# Command.net
KiCad netlist of a schematic drawn in Altium Designer
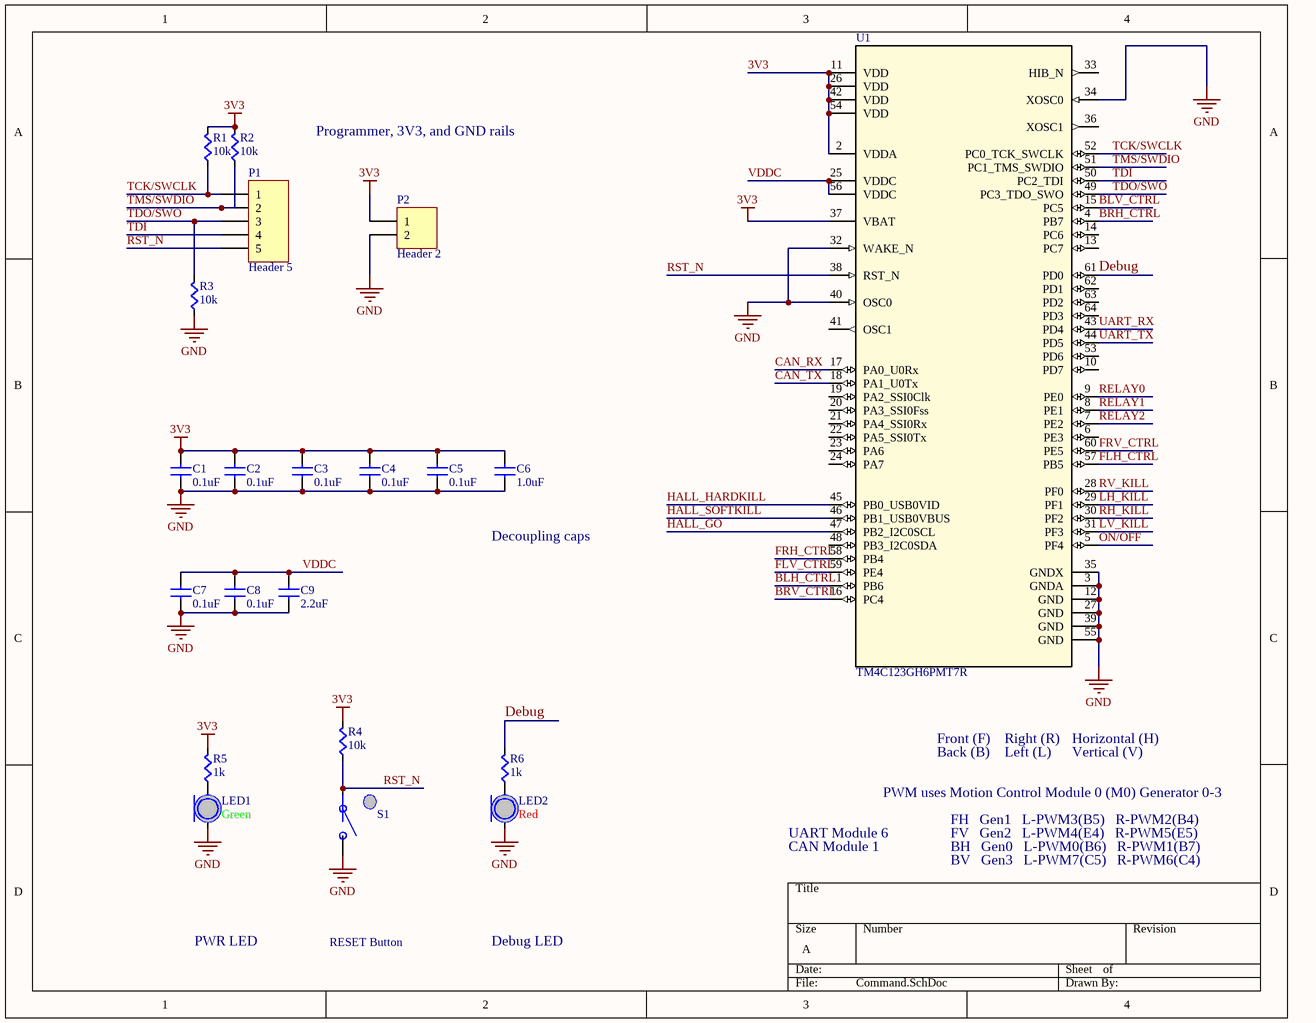
[diagram p0: Command.SchDoc]

(export (version "E")
  (design (tool "Eeschema 10.0.6"))
  (components
    (comp (ref "C1")
      (value "0.1uF")
      (footprint "CAPC0603")
      (fields (field (name "Comment") "Cap"))
      (libsource (lib "SubjuGator8") (part "Cap"))
    )
    (comp (ref "C2")
      (value "0.1uF")
      (footprint "CAPC0603")
      (fields (field (name "Comment") "Cap"))
      (libsource (lib "SubjuGator8") (part "Cap"))
    )
    (comp (ref "C3")
      (value "0.1uF")
      (footprint "CAPC0603")
      (fields (field (name "Comment") "Cap"))
      (libsource (lib "SubjuGator8") (part "Cap"))
    )
    (comp (ref "C4")
      (value "0.1uF")
      (footprint "CAPC0603")
      (fields (field (name "Comment") "Cap"))
      (libsource (lib "SubjuGator8") (part "Cap"))
    )
    (comp (ref "C5")
      (value "0.1uF")
      (footprint "CAPC0603")
      (fields (field (name "Comment") "Cap"))
      (libsource (lib "SubjuGator8") (part "Cap"))
    )
    (comp (ref "C6")
      (value "1.0uF")
      (footprint "CAPC0603")
      (fields (field (name "Comment") "Cap"))
      (libsource (lib "SubjuGator8") (part "Cap"))
    )
    (comp (ref "C7")
      (value "0.1uF")
      (footprint "CAPC0603")
      (fields (field (name "Comment") "Cap"))
      (libsource (lib "SubjuGator8") (part "Cap"))
    )
    (comp (ref "C8")
      (value "0.1uF")
      (footprint "CAPC0603")
      (fields (field (name "Comment") "Cap"))
      (libsource (lib "SubjuGator8") (part "Cap"))
    )
    (comp (ref "C9")
      (value "2.2uF")
      (footprint "CAPC0603")
      (fields (field (name "Comment") "Cap"))
      (libsource (lib "SubjuGator8") (part "Cap"))
    )
    (comp (ref "LED1")
      (value "LED")
      (footprint "LED0603")
      (fields (field (name "COLOR") "Green"))
      (libsource (lib "SubjuGator8") (part "LED"))
    )
    (comp (ref "LED2")
      (value "LED")
      (footprint "LED0603")
      (fields (field (name "COLOR") "Red"))
      (libsource (lib "SubjuGator8") (part "LED"))
    )
    (comp (ref "P1")
      (value "Header 5")
      (footprint "HDR1X5")
      (description "Header, 5-Pin")
      (fields (field (name "PUBLISHER") "Altium Limited"))
      (libsource (lib "Miscellaneous Connectors") (part "Header 5"))
    )
    (comp (ref "P2")
      (value "Header 2")
      (footprint "HDR1X2")
      (description "Header, 2-Pin")
      (fields (field (name "PUBLISHER") "Altium Limited"))
      (libsource (lib "Miscellaneous Connectors") (part "Header 2"))
    )
    (comp (ref "R1")
      (value "10k")
      (footprint "RES0603")
      (fields (field (name "Comment") "Res"))
      (libsource (lib "SubjuGator8") (part "Res"))
    )
    (comp (ref "R2")
      (value "10k")
      (footprint "RES0603")
      (fields (field (name "Comment") "Res"))
      (libsource (lib "SubjuGator8") (part "Res"))
    )
    (comp (ref "R3")
      (value "10k")
      (footprint "RES0603")
      (fields (field (name "Comment") "Res"))
      (libsource (lib "SubjuGator8") (part "Res"))
    )
    (comp (ref "R4")
      (value "10k")
      (footprint "RES0603")
      (fields (field (name "Comment") "Res"))
      (libsource (lib "SubjuGator8") (part "Res"))
    )
    (comp (ref "R5")
      (value "1k")
      (footprint "RES0603")
      (fields (field (name "Comment") "Res"))
      (libsource (lib "SubjuGator8") (part "Res"))
    )
    (comp (ref "R6")
      (value "1k")
      (footprint "RES0603")
      (fields (field (name "Comment") "Res"))
      (libsource (lib "SubjuGator8") (part "Res"))
    )
    (comp (ref "S1")
      (value "Button")
      (footprint "PTS645xxxxSMTR92")
      (description "SPST Button")
      (libsource (lib "SubjuGator8") (part "Button"))
    )
    (comp (ref "U1")
      (value "TM4C123GH6PMT7R")
      (footprint "TM4C123GH6PMT7R_M")
      (description "Imported")
      (fields
        (field (name "PARTNUMBER") "TM4C123GH6PMTR")
        (field (name "ALTERNATE_PARTNUMBER") "TM4C123GH6PMT")
      )
      (libsource (lib "2018-10-31_17-53-54") (part "TM4C123GH6PMT7R"))
    )
  )
  (nets
    (net (code "1") (name "/BLH_CTRL") (class "Default")
      (node (ref "U1") (pin "1") (pinfunction "PB6_1") (pintype "bidirectional"))
    )
    (net (code "2") (name "/BLV_CTRL") (class "Default")
      (node (ref "U1") (pin "15") (pinfunction "PC5_15") (pintype "bidirectional"))
    )
    (net (code "3") (name "/BRH_CTRL") (class "Default")
      (node (ref "U1") (pin "4") (pinfunction "PB7_4") (pintype "bidirectional"))
    )
    (net (code "4") (name "/BRV_CTRL") (class "Default")
      (node (ref "U1") (pin "16") (pinfunction "PC4_16") (pintype "bidirectional"))
    )
    (net (code "5") (name "/CAN_RX") (class "Default")
      (node (ref "U1") (pin "17") (pinfunction "PA0_U0Rx_17") (pintype "bidirectional"))
    )
    (net (code "6") (name "/CAN_TX") (class "Default")
      (node (ref "U1") (pin "18") (pinfunction "PA1_U0Tx_18") (pintype "bidirectional"))
    )
    (net (code "7") (name "/Debug") (class "Default")
      (node (ref "R6") (pin "1") (pinfunction "A_1") (pintype "passive"))
      (node (ref "U1") (pin "61") (pinfunction "PD0_61") (pintype "bidirectional"))
    )
    (net (code "8") (name "/FLH_CTRL") (class "Default")
      (node (ref "U1") (pin "57") (pinfunction "PB5_57") (pintype "bidirectional"))
    )
    (net (code "9") (name "/FLV_CTRL") (class "Default")
      (node (ref "U1") (pin "59") (pinfunction "PE4_59") (pintype "bidirectional"))
    )
    (net (code "10") (name "/FRH_CTRL") (class "Default")
      (node (ref "U1") (pin "58") (pinfunction "PB4_58") (pintype "bidirectional"))
    )
    (net (code "11") (name "/FRV_CTRL") (class "Default")
      (node (ref "U1") (pin "60") (pinfunction "PE5_60") (pintype "bidirectional"))
    )
    (net (code "12") (name "/HALL_GO") (class "Default")
      (node (ref "U1") (pin "47") (pinfunction "PB2_I2C0SCL_47") (pintype "bidirectional"))
    )
    (net (code "13") (name "/HALL_HARDKILL") (class "Default")
      (node (ref "U1") (pin "45") (pinfunction "PB0_USB0VID_45") (pintype "bidirectional"))
    )
    (net (code "14") (name "/HALL_SOFTKILL") (class "Default")
      (node (ref "U1") (pin "46") (pinfunction "PB1_USB0VBUS_46") (pintype "bidirectional"))
    )
    (net (code "15") (name "/LH_KILL") (class "Default")
      (node (ref "U1") (pin "29") (pinfunction "PF1_29") (pintype "bidirectional"))
    )
    (net (code "16") (name "/LV_KILL") (class "Default")
      (node (ref "U1") (pin "31") (pinfunction "PF3_31") (pintype "bidirectional"))
    )
    (net (code "17") (name "/ON{slash}OFF") (class "Default")
      (node (ref "U1") (pin "5") (pinfunction "PF4_5") (pintype "bidirectional"))
    )
    (net (code "18") (name "/RELAY0") (class "Default")
      (node (ref "U1") (pin "9") (pinfunction "PE0_9") (pintype "bidirectional"))
    )
    (net (code "19") (name "/RELAY1") (class "Default")
      (node (ref "U1") (pin "8") (pinfunction "PE1_8") (pintype "bidirectional"))
    )
    (net (code "20") (name "/RELAY2") (class "Default")
      (node (ref "U1") (pin "7") (pinfunction "PE2_7") (pintype "bidirectional"))
    )
    (net (code "21") (name "/RH_KILL") (class "Default")
      (node (ref "U1") (pin "30") (pinfunction "PF2_30") (pintype "bidirectional"))
    )
    (net (code "22") (name "/RST_N") (class "Default")
      (node (ref "P1") (pin "5") (pinfunction "5_5") (pintype "passive"))
      (node (ref "R4") (pin "2") (pinfunction "B_2") (pintype "passive"))
      (node (ref "S1") (pin "A") (pinfunction "A_A") (pintype "passive"))
      (node (ref "U1") (pin "38") (pinfunction "RST_N_38") (pintype "input"))
    )
    (net (code "23") (name "/RV_KILL") (class "Default")
      (node (ref "U1") (pin "28") (pinfunction "PF0_28") (pintype "bidirectional"))
    )
    (net (code "24") (name "/TCK{slash}SWCLK") (class "Default")
      (node (ref "P1") (pin "1") (pinfunction "1_1") (pintype "passive"))
      (node (ref "R1") (pin "2") (pinfunction "B_2") (pintype "passive"))
      (node (ref "U1") (pin "52") (pinfunction "PC0_TCK_SWCLK_52") (pintype "bidirectional"))
    )
    (net (code "25") (name "/TDI") (class "Default")
      (node (ref "P1") (pin "4") (pinfunction "4_4") (pintype "passive"))
      (node (ref "U1") (pin "50") (pinfunction "PC2_TDI_50") (pintype "bidirectional"))
    )
    (net (code "26") (name "/TDO{slash}SWO") (class "Default")
      (node (ref "P1") (pin "3") (pinfunction "3_3") (pintype "passive"))
      (node (ref "R3") (pin "1") (pinfunction "A_1") (pintype "passive"))
      (node (ref "U1") (pin "49") (pinfunction "PC3_TDO_SWO_49") (pintype "bidirectional"))
    )
    (net (code "27") (name "/TMS{slash}SWDIO") (class "Default")
      (node (ref "P1") (pin "2") (pinfunction "2_2") (pintype "passive"))
      (node (ref "R2") (pin "2") (pinfunction "B_2") (pintype "passive"))
      (node (ref "U1") (pin "51") (pinfunction "PC1_TMS_SWDIO_51") (pintype "bidirectional"))
    )
    (net (code "28") (name "/UART_RX") (class "Default")
      (node (ref "U1") (pin "43") (pinfunction "PD4_43") (pintype "bidirectional"))
    )
    (net (code "29") (name "/UART_TX") (class "Default")
      (node (ref "U1") (pin "44") (pinfunction "PD5_44") (pintype "bidirectional"))
    )
    (net (code "30") (name "/VDDC") (class "Default")
      (node (ref "C7") (pin "1") (pinfunction "A_1") (pintype "passive"))
      (node (ref "C8") (pin "1") (pinfunction "A_1") (pintype "passive"))
      (node (ref "C9") (pin "1") (pinfunction "A_1") (pintype "passive"))
      (node (ref "U1") (pin "25") (pinfunction "VDDC_25") (pintype "power_in"))
      (node (ref "U1") (pin "56") (pinfunction "VDDC_56") (pintype "power_in"))
    )
    (net (code "31") (name "3V3") (class "Default")
      (node (ref "C1") (pin "1") (pinfunction "A_1") (pintype "passive"))
      (node (ref "C2") (pin "1") (pinfunction "A_1") (pintype "passive"))
      (node (ref "C3") (pin "1") (pinfunction "A_1") (pintype "passive"))
      (node (ref "C4") (pin "1") (pinfunction "A_1") (pintype "passive"))
      (node (ref "C5") (pin "1") (pinfunction "A_1") (pintype "passive"))
      (node (ref "C6") (pin "1") (pinfunction "A_1") (pintype "passive"))
      (node (ref "P2") (pin "1") (pinfunction "1_1") (pintype "passive"))
      (node (ref "R1") (pin "1") (pinfunction "A_1") (pintype "passive"))
      (node (ref "R2") (pin "1") (pinfunction "A_1") (pintype "passive"))
      (node (ref "R4") (pin "1") (pinfunction "A_1") (pintype "passive"))
      (node (ref "R5") (pin "1") (pinfunction "A_1") (pintype "passive"))
      (node (ref "U1") (pin "11") (pinfunction "VDD_11") (pintype "power_in"))
      (node (ref "U1") (pin "2") (pinfunction "VDDA_2") (pintype "power_in"))
      (node (ref "U1") (pin "26") (pinfunction "VDD_26") (pintype "power_in"))
      (node (ref "U1") (pin "37") (pinfunction "VBAT_37") (pintype "power_in"))
      (node (ref "U1") (pin "42") (pinfunction "VDD_42") (pintype "power_in"))
      (node (ref "U1") (pin "54") (pinfunction "VDD_54") (pintype "power_in"))
    )
    (net (code "32") (name "GND") (class "Default")
      (node (ref "C1") (pin "2") (pinfunction "B_2") (pintype "passive"))
      (node (ref "C2") (pin "2") (pinfunction "B_2") (pintype "passive"))
      (node (ref "C3") (pin "2") (pinfunction "B_2") (pintype "passive"))
      (node (ref "C4") (pin "2") (pinfunction "B_2") (pintype "passive"))
      (node (ref "C5") (pin "2") (pinfunction "B_2") (pintype "passive"))
      (node (ref "C6") (pin "2") (pinfunction "B_2") (pintype "passive"))
      (node (ref "C7") (pin "2") (pinfunction "B_2") (pintype "passive"))
      (node (ref "C8") (pin "2") (pinfunction "B_2") (pintype "passive"))
      (node (ref "C9") (pin "2") (pinfunction "B_2") (pintype "passive"))
      (node (ref "LED1") (pin "C") (pinfunction "C_C") (pintype "passive"))
      (node (ref "LED2") (pin "C") (pinfunction "C_C") (pintype "passive"))
      (node (ref "P2") (pin "2") (pinfunction "2_2") (pintype "passive"))
      (node (ref "R3") (pin "2") (pinfunction "B_2") (pintype "passive"))
      (node (ref "S1") (pin "B") (pinfunction "B_B") (pintype "passive"))
      (node (ref "U1") (pin "12") (pinfunction "GND_12") (pintype "power_in"))
      (node (ref "U1") (pin "27") (pinfunction "GND_27") (pintype "power_in"))
      (node (ref "U1") (pin "3") (pinfunction "GNDA_3") (pintype "power_in"))
      (node (ref "U1") (pin "32") (pinfunction "WAKE_N_32") (pintype "input"))
      (node (ref "U1") (pin "34") (pinfunction "XOSC0_34") (pintype "input"))
      (node (ref "U1") (pin "35") (pinfunction "GNDX_35") (pintype "power_in"))
      (node (ref "U1") (pin "39") (pinfunction "GND_39") (pintype "power_in"))
      (node (ref "U1") (pin "40") (pinfunction "OSC0_40") (pintype "input"))
      (node (ref "U1") (pin "55") (pinfunction "GND_55") (pintype "power_in"))
    )
    (net (code "33") (name "Net-(R5-B)") (class "Default")
      (node (ref "LED1") (pin "A") (pinfunction "A_A") (pintype "passive"))
      (node (ref "R5") (pin "2") (pinfunction "B_2") (pintype "passive"))
    )
    (net (code "34") (name "Net-(R6-B)") (class "Default")
      (node (ref "LED2") (pin "A") (pinfunction "A_A") (pintype "passive"))
      (node (ref "R6") (pin "2") (pinfunction "B_2") (pintype "passive"))
    )
    (net (code "35") (name "unconnected-(U1-HIB_N-Pad33)") (class "Default")
      (node (ref "U1") (pin "33") (pinfunction "HIB_N_33") (pintype "output"))
    )
    (net (code "36") (name "unconnected-(U1-OSC1-Pad41)") (class "Default")
      (node (ref "U1") (pin "41") (pinfunction "OSC1_41") (pintype "output"))
    )
    (net (code "37") (name "unconnected-(U1-PA2_SSI0Clk-Pad19)") (class "Default")
      (node (ref "U1") (pin "19") (pinfunction "PA2_SSI0Clk_19") (pintype "bidirectional"))
    )
    (net (code "38") (name "unconnected-(U1-PA3_SSI0Fss-Pad20)") (class "Default")
      (node (ref "U1") (pin "20") (pinfunction "PA3_SSI0Fss_20") (pintype "bidirectional"))
    )
    (net (code "39") (name "unconnected-(U1-PA4_SSI0Rx-Pad21)") (class "Default")
      (node (ref "U1") (pin "21") (pinfunction "PA4_SSI0Rx_21") (pintype "bidirectional"))
    )
    (net (code "40") (name "unconnected-(U1-PA5_SSI0Tx-Pad22)") (class "Default")
      (node (ref "U1") (pin "22") (pinfunction "PA5_SSI0Tx_22") (pintype "bidirectional"))
    )
    (net (code "41") (name "unconnected-(U1-PA6-Pad23)") (class "Default")
      (node (ref "U1") (pin "23") (pinfunction "PA6_23") (pintype "bidirectional"))
    )
    (net (code "42") (name "unconnected-(U1-PA7-Pad24)") (class "Default")
      (node (ref "U1") (pin "24") (pinfunction "PA7_24") (pintype "bidirectional"))
    )
    (net (code "43") (name "unconnected-(U1-PB3_I2C0SDA-Pad48)") (class "Default")
      (node (ref "U1") (pin "48") (pinfunction "PB3_I2C0SDA_48") (pintype "bidirectional"))
    )
    (net (code "44") (name "unconnected-(U1-PC6-Pad14)") (class "Default")
      (node (ref "U1") (pin "14") (pinfunction "PC6_14") (pintype "bidirectional"))
    )
    (net (code "45") (name "unconnected-(U1-PC7-Pad13)") (class "Default")
      (node (ref "U1") (pin "13") (pinfunction "PC7_13") (pintype "bidirectional"))
    )
    (net (code "46") (name "unconnected-(U1-PD1-Pad62)") (class "Default")
      (node (ref "U1") (pin "62") (pinfunction "PD1_62") (pintype "bidirectional"))
    )
    (net (code "47") (name "unconnected-(U1-PD2-Pad63)") (class "Default")
      (node (ref "U1") (pin "63") (pinfunction "PD2_63") (pintype "bidirectional"))
    )
    (net (code "48") (name "unconnected-(U1-PD3-Pad64)") (class "Default")
      (node (ref "U1") (pin "64") (pinfunction "PD3_64") (pintype "bidirectional"))
    )
    (net (code "49") (name "unconnected-(U1-PD6-Pad53)") (class "Default")
      (node (ref "U1") (pin "53") (pinfunction "PD6_53") (pintype "bidirectional"))
    )
    (net (code "50") (name "unconnected-(U1-PD7-Pad10)") (class "Default")
      (node (ref "U1") (pin "10") (pinfunction "PD7_10") (pintype "bidirectional"))
    )
    (net (code "51") (name "unconnected-(U1-PE3-Pad6)") (class "Default")
      (node (ref "U1") (pin "6") (pinfunction "PE3_6") (pintype "bidirectional"))
    )
    (net (code "52") (name "unconnected-(U1-XOSC1-Pad36)") (class "Default")
      (node (ref "U1") (pin "36") (pinfunction "XOSC1_36") (pintype "output"))
    )
  )
)
